# breakout_green.net
KiCad netlist of a schematic drawn in EAGLE
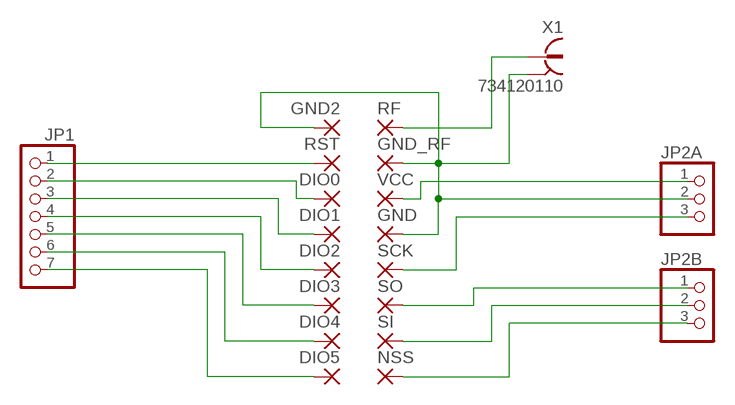
[diagram p0: schematic, sheet 1]

(export (version "E")
  (design (tool "Eeschema 10.0.6"))
  (components
    (comp (ref "DIO0")
      (value "SMD2")
      (footprint "eagle-import:SMD1,27-2,54")
      (libsource (lib "eagle-import") (part "SMD2"))
    )
    (comp (ref "DIO1")
      (value "SMD2")
      (footprint "eagle-import:SMD1,27-2,54")
      (libsource (lib "eagle-import") (part "SMD2"))
    )
    (comp (ref "DIO2")
      (value "SMD2")
      (footprint "eagle-import:SMD1,27-2,54")
      (libsource (lib "eagle-import") (part "SMD2"))
    )
    (comp (ref "DIO3")
      (value "SMD2")
      (footprint "eagle-import:SMD1,27-2,54")
      (libsource (lib "eagle-import") (part "SMD2"))
    )
    (comp (ref "DIO4")
      (value "SMD2")
      (footprint "eagle-import:SMD1,27-2,54")
      (libsource (lib "eagle-import") (part "SMD2"))
    )
    (comp (ref "DIO5")
      (value "SMD2")
      (footprint "eagle-import:SMD1,27-2,54")
      (libsource (lib "eagle-import") (part "SMD2"))
    )
    (comp (ref "GND")
      (value "SMD2")
      (footprint "eagle-import:SMD1,27-2,54")
      (libsource (lib "eagle-import") (part "SMD2"))
    )
    (comp (ref "GND2")
      (value "SMD2")
      (footprint "eagle-import:SMD1,27-2,54")
      (libsource (lib "eagle-import") (part "SMD2"))
    )
    (comp (ref "GND_RF")
      (value "SMD2")
      (footprint "eagle-import:SMD1,27-2,54")
      (libsource (lib "eagle-import") (part "SMD2"))
    )
    (comp (ref "JP1")
      (value "PINHD-1X7")
      (footprint "eagle-import:1X07")
      (libsource (lib "eagle-import") (part "PINHD-1X7"))
    )
    (comp (ref "JP2A")
      (value "PINHD-1X3")
      (footprint "eagle-import:1X03")
      (libsource (lib "eagle-import") (part "PINHD-1X3"))
    )
    (comp (ref "JP2B")
      (value "PINHD-1X3")
      (footprint "eagle-import:1X03")
      (libsource (lib "eagle-import") (part "PINHD-1X3"))
    )
    (comp (ref "NSS")
      (value "SMD2")
      (footprint "eagle-import:SMD1,27-2,54")
      (libsource (lib "eagle-import") (part "SMD2"))
    )
    (comp (ref "RF")
      (value "SMD2")
      (footprint "eagle-import:SMD1,27-2,54")
      (libsource (lib "eagle-import") (part "SMD2"))
    )
    (comp (ref "RST")
      (value "SMD2")
      (footprint "eagle-import:SMD1,27-2,54")
      (libsource (lib "eagle-import") (part "SMD2"))
    )
    (comp (ref "SCK")
      (value "SMD2")
      (footprint "eagle-import:SMD1,27-2,54")
      (libsource (lib "eagle-import") (part "SMD2"))
    )
    (comp (ref "SI")
      (value "SMD2")
      (footprint "eagle-import:SMD1,27-2,54")
      (libsource (lib "eagle-import") (part "SMD2"))
    )
    (comp (ref "SO")
      (value "SMD2")
      (footprint "eagle-import:SMD1,27-2,54")
      (libsource (lib "eagle-import") (part "SMD2"))
    )
    (comp (ref "VCC")
      (value "SMD2")
      (footprint "eagle-import:SMD1,27-2,54")
      (libsource (lib "eagle-import") (part "SMD2"))
    )
    (comp (ref "X1")
      (value "734120110")
      (footprint "eagle-import:734120110")
      (libsource (lib "eagle-import") (part "734120110"))
    )
  )
  (nets
    (net (code "1") (name "Net-(DIO0-P)") (class "Default")
      (node (ref "DIO0") (pin "1") (pinfunction "P_1") (pintype "passive"))
      (node (ref "JP1") (pin "2") (pinfunction "2_2") (pintype "passive"))
    )
    (net (code "2") (name "Net-(DIO1-P)") (class "Default")
      (node (ref "DIO1") (pin "1") (pinfunction "P_1") (pintype "passive"))
      (node (ref "JP1") (pin "3") (pinfunction "3_3") (pintype "passive"))
    )
    (net (code "3") (name "Net-(DIO2-P)") (class "Default")
      (node (ref "DIO2") (pin "1") (pinfunction "P_1") (pintype "passive"))
      (node (ref "JP1") (pin "4") (pinfunction "4_4") (pintype "passive"))
    )
    (net (code "4") (name "Net-(DIO3-P)") (class "Default")
      (node (ref "DIO3") (pin "1") (pinfunction "P_1") (pintype "passive"))
      (node (ref "JP1") (pin "5") (pinfunction "5_5") (pintype "passive"))
    )
    (net (code "5") (name "Net-(DIO4-P)") (class "Default")
      (node (ref "DIO4") (pin "1") (pinfunction "P_1") (pintype "passive"))
      (node (ref "JP1") (pin "6") (pinfunction "6_6") (pintype "passive"))
    )
    (net (code "6") (name "Net-(DIO5-P)") (class "Default")
      (node (ref "DIO5") (pin "1") (pinfunction "P_1") (pintype "passive"))
      (node (ref "JP1") (pin "7") (pinfunction "7_7") (pintype "passive"))
    )
    (net (code "7") (name "Net-(GND-P)") (class "Default")
      (node (ref "GND") (pin "1") (pinfunction "P_1") (pintype "passive"))
      (node (ref "GND2") (pin "1") (pinfunction "P_1") (pintype "passive"))
      (node (ref "GND_RF") (pin "1") (pinfunction "P_1") (pintype "passive"))
      (node (ref "JP2A") (pin "2") (pinfunction "2_2") (pintype "passive"))
      (node (ref "X1") (pin "S@1") (pinfunction "2_S@1") (pintype "passive"))
      (node (ref "X1") (pin "S@2") (pinfunction "2_S@2") (pintype "passive"))
      (node (ref "X1") (pin "S@3") (pinfunction "2_S@3") (pintype "passive"))
    )
    (net (code "8") (name "Net-(NSS-P)") (class "Default")
      (node (ref "JP2B") (pin "3") (pinfunction "3_3") (pintype "passive"))
      (node (ref "NSS") (pin "1") (pinfunction "P_1") (pintype "passive"))
    )
    (net (code "9") (name "Net-(RF-P)") (class "Default")
      (node (ref "RF") (pin "1") (pinfunction "P_1") (pintype "passive"))
      (node (ref "X1") (pin "1") (pinfunction "1_1") (pintype "passive"))
    )
    (net (code "10") (name "Net-(RST-P)") (class "Default")
      (node (ref "JP1") (pin "1") (pinfunction "1_1") (pintype "passive"))
      (node (ref "RST") (pin "1") (pinfunction "P_1") (pintype "passive"))
    )
    (net (code "11") (name "Net-(SCK-P)") (class "Default")
      (node (ref "JP2A") (pin "3") (pinfunction "3_3") (pintype "passive"))
      (node (ref "SCK") (pin "1") (pinfunction "P_1") (pintype "passive"))
    )
    (net (code "12") (name "Net-(SI-P)") (class "Default")
      (node (ref "JP2B") (pin "2") (pinfunction "2_2") (pintype "passive"))
      (node (ref "SI") (pin "1") (pinfunction "P_1") (pintype "passive"))
    )
    (net (code "13") (name "Net-(SO-P)") (class "Default")
      (node (ref "JP2B") (pin "1") (pinfunction "1_1") (pintype "passive"))
      (node (ref "SO") (pin "1") (pinfunction "P_1") (pintype "passive"))
    )
    (net (code "14") (name "Net-(VCC-P)") (class "Default")
      (node (ref "JP2A") (pin "1") (pinfunction "1_1") (pintype "passive"))
      (node (ref "VCC") (pin "1") (pinfunction "P_1") (pintype "passive"))
    )
  )
)
